# SuperKnob.net
KiCad netlist of a schematic drawn in Altium Designer
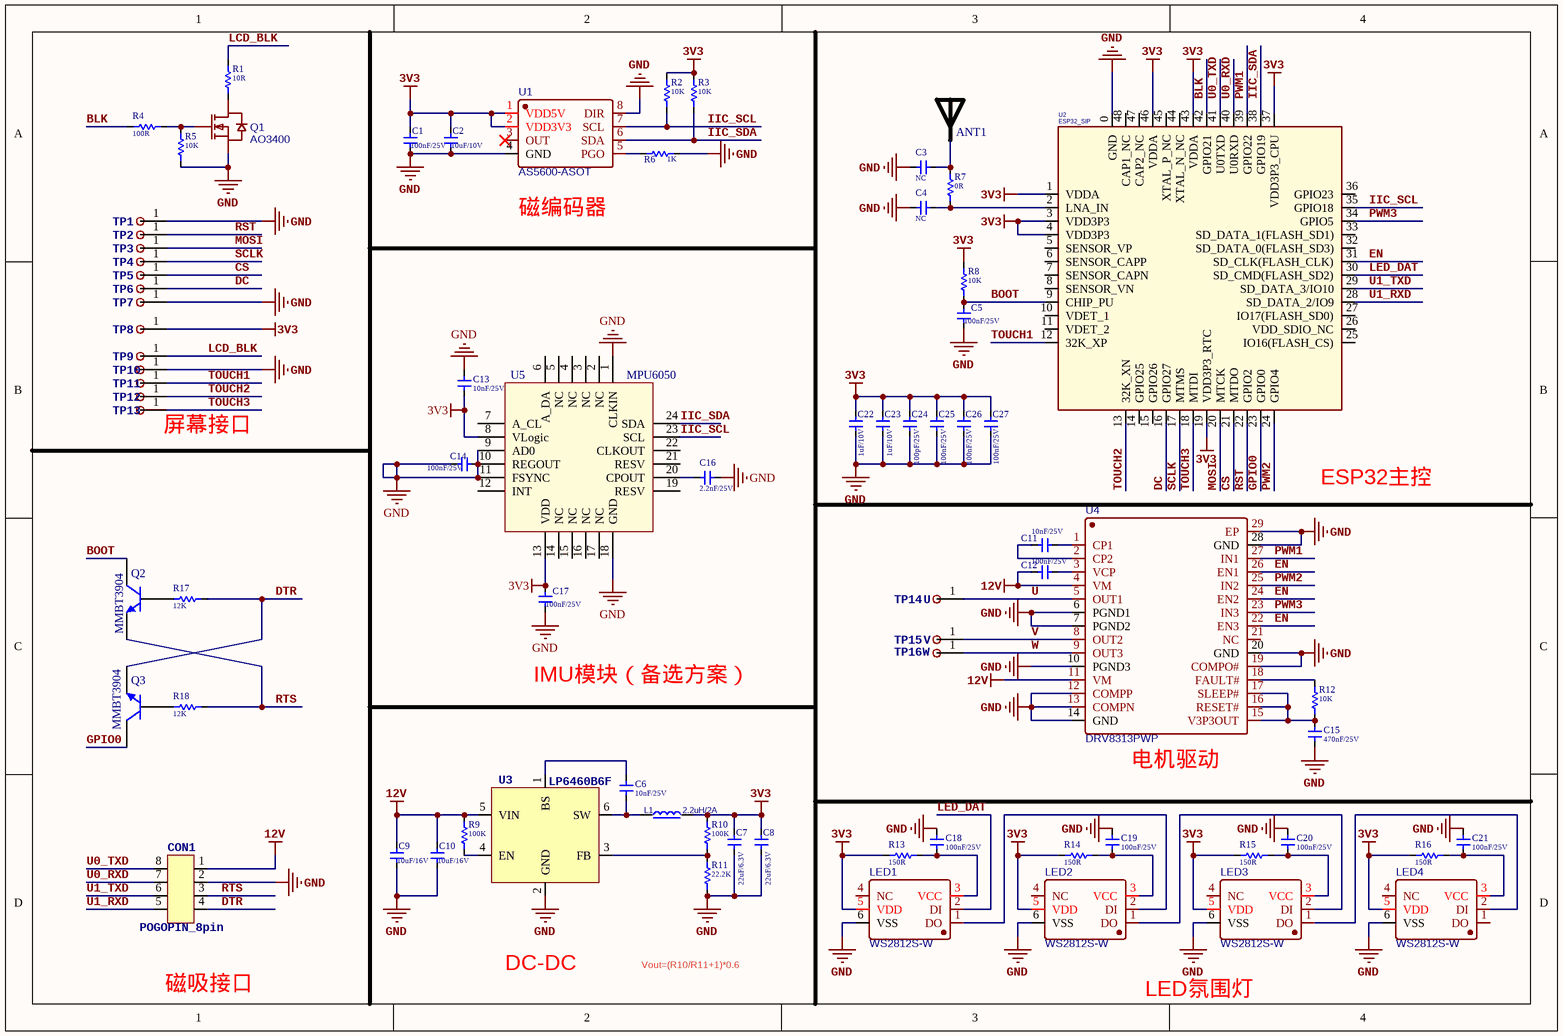
[diagram p0: SuperKnob.SchDoc]

(export (version "E")
  (design (tool "Eeschema 10.0.6"))
  (components
    (comp (ref "ANT1")
      (value "RAINSUN")
      (footprint "ANT-Rainsun-AN5120")
      (description "贴片天线")
      (libsource (lib "SuperKnob") (part "ANT-Rainsun-AP5120"))
    )
    (comp (ref "C1")
      (value "100nF/25V")
      (footprint "CAPC_0402")
      (description "贴片电容")
      (libsource (lib "SuperKnob") (part "电容-0402"))
    )
    (comp (ref "C2")
      (value "10uF/10V")
      (footprint "CAPC_0402")
      (description "贴片电容")
      (libsource (lib "SuperKnob") (part "电容-0402"))
    )
    (comp (ref "C3")
      (value "NC")
      (footprint "CAPC_0402")
      (description "贴片电容")
      (libsource (lib "SuperKnob") (part "电容-0402"))
    )
    (comp (ref "C4")
      (value "NC")
      (footprint "CAPC_0402")
      (description "贴片电容")
      (libsource (lib "SuperKnob") (part "电容-0402"))
    )
    (comp (ref "C5")
      (value "100nF/25V")
      (footprint "CAPC_0402")
      (description "贴片电容")
      (libsource (lib "SuperKnob") (part "电容-0402"))
    )
    (comp (ref "C6")
      (value "10nF/25V")
      (footprint "CAPC_0402")
      (description "贴片电容")
      (libsource (lib "SuperKnob") (part "电容-0402"))
    )
    (comp (ref "C7")
      (value "22uF/6.3V")
      (footprint "CAPC_0805")
      (description "贴片电容")
      (libsource (lib "SuperKnob") (part "电容-0402"))
    )
    (comp (ref "C8")
      (value "22uF/6.3V")
      (footprint "CAPC_0805")
      (description "贴片电容")
      (libsource (lib "SuperKnob") (part "电容-0402"))
    )
    (comp (ref "C9")
      (value "10uF/16V")
      (footprint "CAPC_0805")
      (description "贴片电容")
      (libsource (lib "SuperKnob") (part "电容-0402"))
    )
    (comp (ref "C10")
      (value "10uF/16V")
      (footprint "CAPC_0805")
      (description "贴片电容")
      (libsource (lib "SuperKnob") (part "电容-0402"))
    )
    (comp (ref "C11")
      (value "10nF/25V")
      (footprint "CAPC_0402")
      (description "贴片电容")
      (libsource (lib "SuperKnob") (part "电容-0402"))
    )
    (comp (ref "C12")
      (value "100nF/25V")
      (footprint "CAPC_0402")
      (description "贴片电容")
      (libsource (lib "SuperKnob") (part "电容-0402"))
    )
    (comp (ref "C13")
      (value "10nF/25V")
      (footprint "CAPC_0402")
      (description "贴片电容")
      (libsource (lib "SuperKnob") (part "电容-0402"))
    )
    (comp (ref "C14")
      (value "100nF/25V")
      (footprint "CAPC_0402")
      (description "贴片电容")
      (libsource (lib "SuperKnob") (part "电容-0402"))
    )
    (comp (ref "C15")
      (value "470nF/25V")
      (footprint "CAPC_0402")
      (description "贴片电容")
      (libsource (lib "SuperKnob") (part "电容-0402"))
    )
    (comp (ref "C16")
      (value "2.2nF/25V")
      (footprint "CAPC_0402")
      (description "贴片电容")
      (libsource (lib "SuperKnob") (part "电容-0402"))
    )
    (comp (ref "C17")
      (value "100nF/25V")
      (footprint "CAPC_0402")
      (description "贴片电容")
      (libsource (lib "SuperKnob") (part "电容-0402"))
    )
    (comp (ref "C18")
      (value "100nF/25V")
      (footprint "CAPC_0402")
      (description "贴片电容")
      (libsource (lib "SuperKnob") (part "电容-0402"))
    )
    (comp (ref "C19")
      (value "100nF/25V")
      (footprint "CAPC_0402")
      (description "贴片电容")
      (libsource (lib "SuperKnob") (part "电容-0402"))
    )
    (comp (ref "C20")
      (value "100nF/25V")
      (footprint "CAPC_0402")
      (description "贴片电容")
      (libsource (lib "SuperKnob") (part "电容-0402"))
    )
    (comp (ref "C21")
      (value "100nF/25V")
      (footprint "CAPC_0402")
      (description "贴片电容")
      (libsource (lib "SuperKnob") (part "电容-0402"))
    )
    (comp (ref "C22")
      (value "1uF/10V")
      (footprint "CAPC_0402")
      (description "贴片电容")
      (libsource (lib "SuperKnob") (part "电容-0402"))
    )
    (comp (ref "C23")
      (value "1uF/10V")
      (footprint "CAPC_0402")
      (description "贴片电容")
      (libsource (lib "SuperKnob") (part "电容-0402"))
    )
    (comp (ref "C24")
      (value "100pF/25V")
      (footprint "CAPC_0402")
      (description "贴片电容")
      (libsource (lib "SuperKnob") (part "电容-0402"))
    )
    (comp (ref "C25")
      (value "100nF/25V")
      (footprint "CAPC_0402")
      (description "贴片电容")
      (libsource (lib "SuperKnob") (part "电容-0402"))
    )
    (comp (ref "C26")
      (value "100nF/25V")
      (footprint "CAPC_0402")
      (description "贴片电容")
      (libsource (lib "SuperKnob") (part "电容-0402"))
    )
    (comp (ref "C27")
      (value "100nF/25V")
      (footprint "CAPC_0402")
      (description "贴片电容")
      (libsource (lib "SuperKnob") (part "电容-0402"))
    )
    (comp (ref "CON1")
      (value "POGOPIN_8pin")
      (footprint "POGOPIN_8pin")
      (description "磁吸连接器")
      (libsource (lib "SuperKnob") (part "POGOPIN_8pin"))
    )
    (comp (ref "L1")
      (value "2.2uH/2A")
      (footprint "Inductor_CD_43")
      (description "贴片电感")
      (libsource (lib "*") (part "PL4020"))
    )
    (comp (ref "LED1")
      (value "WS2812S-W")
      (footprint "LED-SMD_6P-L5.0-W5.0-TL")
      (fields (field (name "BOM_SUPPLIER PART") "C114584") (field (name "CONTRIBUTOR") "LCSC"))
      (libsource (lib "altium-import") (part "root_2_WS2812S-W_"))
    )
    (comp (ref "LED2")
      (value "WS2812S-W")
      (footprint "LED-SMD_6P-L5.0-W5.0-TL")
      (fields (field (name "BOM_SUPPLIER PART") "C114584") (field (name "CONTRIBUTOR") "LCSC"))
      (libsource (lib "altium-import") (part "root_2_WS2812S-W_"))
    )
    (comp (ref "LED3")
      (value "WS2812S-W")
      (footprint "LED-SMD_6P-L5.0-W5.0-TL")
      (fields (field (name "BOM_SUPPLIER PART") "C114584") (field (name "CONTRIBUTOR") "LCSC"))
      (libsource (lib "altium-import") (part "root_2_WS2812S-W_"))
    )
    (comp (ref "LED4")
      (value "WS2812S-W")
      (footprint "LED-SMD_6P-L5.0-W5.0-TL")
      (fields (field (name "BOM_SUPPLIER PART") "C114584") (field (name "CONTRIBUTOR") "LCSC"))
      (libsource (lib "altium-import") (part "root_2_WS2812S-W_"))
    )
    (comp (ref "Q1")
      (value "AO3400")
      (footprint "SOT23_3")
      (fields
        (field (name "BOM_SUPPLIER PART") "C2940037")
        (field (name "BOM_MANUFACTURER PART") "FH3400C")
        (field (name "CONTRIBUTOR") "LCSC")
      )
      (libsource (lib "altium-import") (part "root_0_FH3400C_"))
    )
    (comp (ref "Q2")
      (value "MMBT3904")
      (footprint "SOT23_3")
      (description "Surface mount NPN transistor, package SOT-23")
      (libsource (lib "MyPcbLib") (part "SMT_TRIODE_NPN"))
    )
    (comp (ref "Q3")
      (value "MMBT3904")
      (footprint "SOT23_3")
      (description "Surface mount NPN transistor, package SOT-23")
      (libsource (lib "MyPcbLib") (part "SMT_TRIODE_NPN"))
    )
    (comp (ref "R1")
      (value "10R")
      (footprint "RESC_0402")
      (description "贴片电阻")
      (libsource (lib "SuperKnob") (part "电阻-0402"))
    )
    (comp (ref "R2")
      (value "10K")
      (footprint "RESC_0402")
      (description "贴片电阻")
      (libsource (lib "SuperKnob") (part "电阻-0402"))
    )
    (comp (ref "R3")
      (value "10K")
      (footprint "RESC_0402")
      (description "贴片电阻")
      (libsource (lib "SuperKnob") (part "电阻-0402"))
    )
    (comp (ref "R4")
      (value "100R")
      (footprint "RESC_0402")
      (description "贴片电阻")
      (libsource (lib "SuperKnob") (part "电阻-0402"))
    )
    (comp (ref "R5")
      (value "10K")
      (footprint "RESC_0402")
      (description "贴片电阻")
      (libsource (lib "SuperKnob") (part "电阻-0402"))
    )
    (comp (ref "R6")
      (value "1K")
      (footprint "RESC_0402")
      (description "贴片电阻")
      (libsource (lib "SuperKnob") (part "电阻-0402"))
    )
    (comp (ref "R7")
      (value "0R")
      (footprint "RESC_0402")
      (description "贴片电阻")
      (libsource (lib "SuperKnob") (part "电阻-0402"))
    )
    (comp (ref "R8")
      (value "10K")
      (footprint "RESC_0402")
      (description "贴片电阻")
      (libsource (lib "SuperKnob") (part "电阻-0402"))
    )
    (comp (ref "R9")
      (value "100K")
      (footprint "RESC_0402")
      (description "贴片电阻")
      (libsource (lib "SuperKnob") (part "电阻-0402"))
    )
    (comp (ref "R10")
      (value "100K")
      (footprint "RESC_0402")
      (description "贴片电阻")
      (libsource (lib "SuperKnob") (part "电阻-0402"))
    )
    (comp (ref "R11")
      (value "22.2K")
      (footprint "RESC_0402")
      (description "贴片电阻")
      (libsource (lib "SuperKnob") (part "电阻-0402"))
    )
    (comp (ref "R12")
      (value "10K")
      (footprint "RESC_0402")
      (description "贴片电阻")
      (libsource (lib "SuperKnob") (part "电阻-0402"))
    )
    (comp (ref "R13")
      (value "150R")
      (footprint "RESC_0603")
      (description "贴片电阻")
      (libsource (lib "SuperKnob") (part "电阻-0402"))
    )
    (comp (ref "R14")
      (value "150R")
      (footprint "RESC_0603")
      (description "贴片电阻")
      (libsource (lib "SuperKnob") (part "电阻-0402"))
    )
    (comp (ref "R15")
      (value "150R")
      (footprint "RESC_0603")
      (description "贴片电阻")
      (libsource (lib "SuperKnob") (part "电阻-0402"))
    )
    (comp (ref "R16")
      (value "150R")
      (footprint "RESC_0603")
      (description "贴片电阻")
      (libsource (lib "SuperKnob") (part "电阻-0402"))
    )
    (comp (ref "R17")
      (value "12K")
      (footprint "RESC_0402")
      (description "贴片电阻")
      (libsource (lib "SuperKnob") (part "电阻-0402"))
    )
    (comp (ref "R18")
      (value "12K")
      (footprint "RESC_0402")
      (description "贴片电阻")
      (libsource (lib "SuperKnob") (part "电阻-0402"))
    )
    (comp (ref "TP1")
      (value "TP")
      (footprint "TP")
      (description "测试点")
      (libsource (lib "SuperKnob") (part "TP"))
    )
    (comp (ref "TP2")
      (value "TP")
      (footprint "TP")
      (description "测试点")
      (libsource (lib "SuperKnob") (part "TP"))
    )
    (comp (ref "TP3")
      (value "TP")
      (footprint "TP")
      (description "测试点")
      (libsource (lib "SuperKnob") (part "TP"))
    )
    (comp (ref "TP4")
      (value "TP")
      (footprint "TP")
      (description "测试点")
      (libsource (lib "SuperKnob") (part "TP"))
    )
    (comp (ref "TP5")
      (value "TP")
      (footprint "TP")
      (description "测试点")
      (libsource (lib "SuperKnob") (part "TP"))
    )
    (comp (ref "TP6")
      (value "TP")
      (footprint "TP")
      (description "测试点")
      (libsource (lib "SuperKnob") (part "TP"))
    )
    (comp (ref "TP7")
      (value "TP")
      (footprint "TP")
      (description "测试点")
      (libsource (lib "SuperKnob") (part "TP"))
    )
    (comp (ref "TP8")
      (value "TP")
      (footprint "TP")
      (description "测试点")
      (libsource (lib "SuperKnob") (part "TP"))
    )
    (comp (ref "TP9")
      (value "TP")
      (footprint "TP")
      (description "测试点")
      (libsource (lib "SuperKnob") (part "TP"))
    )
    (comp (ref "TP10")
      (value "TP")
      (footprint "TP")
      (description "测试点")
      (libsource (lib "SuperKnob") (part "TP"))
    )
    (comp (ref "TP11")
      (value "TP")
      (footprint "TP")
      (description "测试点")
      (libsource (lib "SuperKnob") (part "TP"))
    )
    (comp (ref "TP12")
      (value "TP")
      (footprint "TP")
      (description "测试点")
      (libsource (lib "SuperKnob") (part "TP"))
    )
    (comp (ref "TP13")
      (value "TP")
      (footprint "TP")
      (description "测试点")
      (libsource (lib "SuperKnob") (part "TP"))
    )
    (comp (ref "TP14")
      (value "U")
      (footprint "TP")
      (description "测试点")
      (libsource (lib "SuperKnob") (part "TP"))
    )
    (comp (ref "TP15")
      (value "V")
      (footprint "TP")
      (description "测试点")
      (libsource (lib "SuperKnob") (part "TP"))
    )
    (comp (ref "TP16")
      (value "W")
      (footprint "TP")
      (description "测试点")
      (libsource (lib "SuperKnob") (part "TP"))
    )
    (comp (ref "U1")
      (value "AS5600-ASOT")
      (footprint "SOIC_8")
      (description "磁编码器")
      (fields (field (name "BOM_SUPPLIER PART") "C499458") (field (name "CONTRIBUTOR") "LCSC"))
      (libsource (lib "SuperKnob") (part "AS5600-ASOT"))
    )
    (comp (ref "U2")
      (value "ESP32_SIP")
      (footprint "QFN-48_7X7")
      (description "主控芯片")
      (libsource (lib "SuperKnob") (part "ESP32-PICO"))
    )
    (comp (ref "U3")
      (value "LP6460B6F")
      (footprint "SOT23_6")
      (description "DC-DC芯片")
      (libsource (lib "SuperKnob") (part "LP6460B6F"))
    )
    (comp (ref "U4")
      (value "DRV8313PWP")
      (footprint "TSSOP_28")
      (description "驱动芯片")
      (fields (field (name "BOM_SUPPLIER PART") "C2863441") (field (name "CONTRIBUTOR") "LCSC"))
      (libsource (lib "SuperKnob") (part "DRV8313PWP"))
    )
    (comp (ref "U5")
      (value "MPU6050")
      (footprint "QFN-24")
      (description "六轴传感器")
      (libsource (lib "mLib") (part "MPU6050"))
    )
  )
  (nets
    (net (code "1") (name "/BLK") (class "Default")
      (node (ref "R4") (pin "1") (pinfunction "1_1") (pintype "passive"))
      (node (ref "U2") (pin "42") (pinfunction "GPIO21_42") (pintype "passive"))
    )
    (net (code "2") (name "/BOOT") (class "Default")
      (node (ref "C5") (pin "2") (pinfunction "2_2") (pintype "passive"))
      (node (ref "Q2") (pin "3") (pinfunction "C_3") (pintype "passive"))
      (node (ref "R8") (pin "2") (pinfunction "2_2") (pintype "passive"))
      (node (ref "U2") (pin "9") (pinfunction "CHIP_PU_9") (pintype "passive"))
    )
    (net (code "3") (name "/CS") (class "Default")
      (node (ref "TP5") (pin "1") (pinfunction "1_1") (pintype "passive"))
      (node (ref "U2") (pin "21") (pinfunction "MTDO_21") (pintype "passive"))
    )
    (net (code "4") (name "/DC") (class "Default")
      (node (ref "TP6") (pin "1") (pinfunction "1_1") (pintype "passive"))
      (node (ref "U2") (pin "16") (pinfunction "GPIO27_16") (pintype "passive"))
    )
    (net (code "5") (name "/DTR") (class "Default")
      (node (ref "CON1") (pin "4") (pinfunction "4_4") (pintype "passive"))
      (node (ref "Q3") (pin "2") (pinfunction "E_2") (pintype "passive"))
      (node (ref "R17") (pin "2") (pinfunction "2_2") (pintype "passive"))
    )
    (net (code "6") (name "/EN") (class "Default")
      (node (ref "U2") (pin "31") (pinfunction "SD_CLK(FLASH_CLK)_31") (pintype "passive"))
      (node (ref "U4") (pin "22") (pinfunction "EN3_22") (pintype "passive"))
      (node (ref "U4") (pin "24") (pinfunction "EN2_24") (pintype "passive"))
      (node (ref "U4") (pin "26") (pinfunction "EN1_26") (pintype "passive"))
    )
    (net (code "7") (name "/GPIO0") (class "Default")
      (node (ref "Q3") (pin "3") (pinfunction "C_3") (pintype "passive"))
      (node (ref "U2") (pin "23") (pinfunction "GPIO0_23") (pintype "passive"))
    )
    (net (code "8") (name "/IIC_SCL") (class "Default")
      (node (ref "R2") (pin "1") (pinfunction "1_1") (pintype "passive"))
      (node (ref "U1") (pin "7") (pinfunction "SCL_7") (pintype "passive"))
      (node (ref "U2") (pin "35") (pinfunction "GPIO18_35") (pintype "passive"))
      (node (ref "U5") (pin "23") (pinfunction "SCL_23") (pintype "passive"))
    )
    (net (code "9") (name "/IIC_SDA") (class "Default")
      (node (ref "R3") (pin "1") (pinfunction "1_1") (pintype "passive"))
      (node (ref "U1") (pin "6") (pinfunction "SDA_6") (pintype "passive"))
      (node (ref "U2") (pin "38") (pinfunction "GPIO19_38") (pintype "passive"))
      (node (ref "U5") (pin "24") (pinfunction "SDA_24") (pintype "passive"))
    )
    (net (code "10") (name "/LCD_BLK") (class "Default")
      (node (ref "R1") (pin "2") (pinfunction "2_2") (pintype "passive"))
      (node (ref "TP9") (pin "1") (pinfunction "1_1") (pintype "passive"))
    )
    (net (code "11") (name "/LED_DAT") (class "Default")
      (node (ref "LED1") (pin "2") (pinfunction "DI_2") (pintype "passive"))
      (node (ref "U2") (pin "30") (pinfunction "SD_CMD(FLASH_SD2)_30") (pintype "passive"))
    )
    (net (code "12") (name "/MOSI") (class "Default")
      (node (ref "TP3") (pin "1") (pinfunction "1_1") (pintype "passive"))
      (node (ref "U2") (pin "20") (pinfunction "MTCK_20") (pintype "passive"))
    )
    (net (code "13") (name "/PWM1") (class "Default")
      (node (ref "U2") (pin "39") (pinfunction "GPIO22_39") (pintype "passive"))
      (node (ref "U4") (pin "27") (pinfunction "IN1_27") (pintype "passive"))
    )
    (net (code "14") (name "/PWM2") (class "Default")
      (node (ref "U2") (pin "24") (pinfunction "GPIO4_24") (pintype "passive"))
      (node (ref "U4") (pin "25") (pinfunction "IN2_25") (pintype "passive"))
    )
    (net (code "15") (name "/PWM3") (class "Default")
      (node (ref "U2") (pin "34") (pinfunction "GPIO5_34") (pintype "passive"))
      (node (ref "U4") (pin "23") (pinfunction "IN3_23") (pintype "passive"))
    )
    (net (code "16") (name "/RST") (class "Default")
      (node (ref "TP2") (pin "1") (pinfunction "1_1") (pintype "passive"))
      (node (ref "U2") (pin "22") (pinfunction "GPIO2_22") (pintype "passive"))
    )
    (net (code "17") (name "/RTS") (class "Default")
      (node (ref "CON1") (pin "3") (pinfunction "3_3") (pintype "passive"))
      (node (ref "Q2") (pin "2") (pinfunction "E_2") (pintype "passive"))
      (node (ref "R18") (pin "2") (pinfunction "2_2") (pintype "passive"))
    )
    (net (code "18") (name "/SCLK") (class "Default")
      (node (ref "TP4") (pin "1") (pinfunction "1_1") (pintype "passive"))
      (node (ref "U2") (pin "17") (pinfunction "MTMS_17") (pintype "passive"))
    )
    (net (code "19") (name "/TOUCH1") (class "Default")
      (node (ref "TP11") (pin "1") (pinfunction "1_1") (pintype "passive"))
      (node (ref "U2") (pin "12") (pinfunction "32K_XP_12") (pintype "passive"))
    )
    (net (code "20") (name "/TOUCH2") (class "Default")
      (node (ref "TP12") (pin "1") (pinfunction "1_1") (pintype "passive"))
      (node (ref "U2") (pin "13") (pinfunction "32K_XN_13") (pintype "passive"))
    )
    (net (code "21") (name "/TOUCH3") (class "Default")
      (node (ref "TP13") (pin "1") (pinfunction "1_1") (pintype "passive"))
      (node (ref "U2") (pin "18") (pinfunction "MTDI_18") (pintype "passive"))
    )
    (net (code "22") (name "/U") (class "Default")
      (node (ref "TP14") (pin "1") (pinfunction "1_1") (pintype "passive"))
      (node (ref "U4") (pin "5") (pinfunction "OUT1_5") (pintype "passive"))
    )
    (net (code "23") (name "/U0_RXD") (class "Default")
      (node (ref "CON1") (pin "7") (pinfunction "7_7") (pintype "passive"))
      (node (ref "U2") (pin "40") (pinfunction "U0RXD_40") (pintype "power_in"))
    )
    (net (code "24") (name "/U0_TXD") (class "Default")
      (node (ref "CON1") (pin "8") (pinfunction "8_8") (pintype "passive"))
      (node (ref "U2") (pin "41") (pinfunction "U0TXD_41") (pintype "power_in"))
    )
    (net (code "25") (name "/U1_RXD") (class "Default")
      (node (ref "CON1") (pin "5") (pinfunction "5_5") (pintype "passive"))
      (node (ref "U2") (pin "28") (pinfunction "SD_DATA_2/IO9_28") (pintype "passive"))
    )
    (net (code "26") (name "/U1_TXD") (class "Default")
      (node (ref "CON1") (pin "6") (pinfunction "6_6") (pintype "passive"))
      (node (ref "U2") (pin "29") (pinfunction "SD_DATA_3/IO10_29") (pintype "passive"))
    )
    (net (code "27") (name "/V") (class "Default")
      (node (ref "TP15") (pin "1") (pinfunction "1_1") (pintype "passive"))
      (node (ref "U4") (pin "8") (pinfunction "OUT2_8") (pintype "passive"))
    )
    (net (code "28") (name "/W") (class "Default")
      (node (ref "TP16") (pin "1") (pinfunction "1_1") (pintype "passive"))
      (node (ref "U4") (pin "9") (pinfunction "OUT3_9") (pintype "passive"))
    )
    (net (code "29") (name "3V3") (class "Default")
      (node (ref "C1") (pin "2") (pinfunction "2_2") (pintype "passive"))
      (node (ref "C13") (pin "2") (pinfunction "2_2") (pintype "passive"))
      (node (ref "C17") (pin "2") (pinfunction "2_2") (pintype "passive"))
      (node (ref "C2") (pin "2") (pinfunction "2_2") (pintype "passive"))
      (node (ref "C22") (pin "2") (pinfunction "2_2") (pintype "passive"))
      (node (ref "C23") (pin "2") (pinfunction "2_2") (pintype "passive"))
      (node (ref "C24") (pin "1") (pinfunction "1_1") (pintype "passive"))
      (node (ref "C25") (pin "2") (pinfunction "2_2") (pintype "passive"))
      (node (ref "C26") (pin "2") (pinfunction "2_2") (pintype "passive"))
      (node (ref "C27") (pin "2") (pinfunction "2_2") (pintype "passive"))
      (node (ref "C7") (pin "2") (pinfunction "2_2") (pintype "passive"))
      (node (ref "C8") (pin "2") (pinfunction "2_2") (pintype "passive"))
      (node (ref "L1") (pin "1") (pinfunction "1_1") (pintype "passive"))
      (node (ref "LED1") (pin "5") (pinfunction "VDD_5") (pintype "passive"))
      (node (ref "LED2") (pin "5") (pinfunction "VDD_5") (pintype "passive"))
      (node (ref "LED3") (pin "5") (pinfunction "VDD_5") (pintype "passive"))
      (node (ref "LED4") (pin "5") (pinfunction "VDD_5") (pintype "passive"))
      (node (ref "R10") (pin "1") (pinfunction "1_1") (pintype "passive"))
      (node (ref "R13") (pin "1") (pinfunction "1_1") (pintype "passive"))
      (node (ref "R14") (pin "1") (pinfunction "1_1") (pintype "passive"))
      (node (ref "R15") (pin "1") (pinfunction "1_1") (pintype "passive"))
      (node (ref "R16") (pin "1") (pinfunction "1_1") (pintype "passive"))
      (node (ref "R2") (pin "2") (pinfunction "2_2") (pintype "passive"))
      (node (ref "R3") (pin "2") (pinfunction "2_2") (pintype "passive"))
      (node (ref "R8") (pin "1") (pinfunction "1_1") (pintype "passive"))
      (node (ref "TP8") (pin "1") (pinfunction "1_1") (pintype "passive"))
      (node (ref "U1") (pin "1") (pinfunction "VDD5V_1") (pintype "passive"))
      (node (ref "U1") (pin "2") (pinfunction "VDD3V3_2") (pintype "passive"))
      (node (ref "U2") (pin "1") (pinfunction "VDDA_1") (pintype "power_in"))
      (node (ref "U2") (pin "19") (pinfunction "VDD3P3_RTC_19") (pintype "power_in"))
      (node (ref "U2") (pin "3") (pinfunction "VDD3P3_3") (pintype "power_in"))
      (node (ref "U2") (pin "37") (pinfunction "VDD3P3_CPU_37") (pintype "power_in"))
      (node (ref "U2") (pin "4") (pinfunction "VDD3P3_4") (pintype "power_in"))
      (node (ref "U2") (pin "43") (pinfunction "VDDA_43") (pintype "power_in"))
      (node (ref "U2") (pin "46") (pinfunction "VDDA_46") (pintype "power_in"))
      (node (ref "U5") (pin "13") (pinfunction "VDD_13") (pintype "passive"))
      (node (ref "U5") (pin "8") (pinfunction "VLogic_8") (pintype "passive"))
    )
    (net (code "30") (name "12V") (class "Default")
      (node (ref "C10") (pin "2") (pinfunction "2_2") (pintype "passive"))
      (node (ref "C12") (pin "1") (pinfunction "1_1") (pintype "passive"))
      (node (ref "C9") (pin "2") (pinfunction "2_2") (pintype "passive"))
      (node (ref "CON1") (pin "1") (pinfunction "1_1") (pintype "passive"))
      (node (ref "R9") (pin "1") (pinfunction "1_1") (pintype "passive"))
      (node (ref "U3") (pin "5") (pinfunction "VIN_5") (pintype "passive"))
      (node (ref "U4") (pin "11") (pinfunction "VM_11") (pintype "passive"))
      (node (ref "U4") (pin "4") (pinfunction "VM_4") (pintype "passive"))
    )
    (net (code "31") (name "GND") (class "Default")
      (node (ref "C1") (pin "1") (pinfunction "1_1") (pintype "passive"))
      (node (ref "C10") (pin "1") (pinfunction "1_1") (pintype "passive"))
      (node (ref "C13") (pin "1") (pinfunction "1_1") (pintype "passive"))
      (node (ref "C14") (pin "1") (pinfunction "1_1") (pintype "passive"))
      (node (ref "C14") (pin "2") (pinfunction "2_2") (pintype "passive"))
      (node (ref "C15") (pin "1") (pinfunction "1_1") (pintype "passive"))
      (node (ref "C16") (pin "2") (pinfunction "2_2") (pintype "passive"))
      (node (ref "C17") (pin "1") (pinfunction "1_1") (pintype "passive"))
      (node (ref "C18") (pin "2") (pinfunction "2_2") (pintype "passive"))
      (node (ref "C19") (pin "2") (pinfunction "2_2") (pintype "passive"))
      (node (ref "C2") (pin "1") (pinfunction "1_1") (pintype "passive"))
      (node (ref "C20") (pin "1") (pinfunction "1_1") (pintype "passive"))
      (node (ref "C21") (pin "1") (pinfunction "1_1") (pintype "passive"))
      (node (ref "C22") (pin "1") (pinfunction "1_1") (pintype "passive"))
      (node (ref "C23") (pin "1") (pinfunction "1_1") (pintype "passive"))
      (node (ref "C24") (pin "2") (pinfunction "2_2") (pintype "passive"))
      (node (ref "C25") (pin "1") (pinfunction "1_1") (pintype "passive"))
      (node (ref "C26") (pin "1") (pinfunction "1_1") (pintype "passive"))
      (node (ref "C27") (pin "1") (pinfunction "1_1") (pintype "passive"))
      (node (ref "C3") (pin "1") (pinfunction "1_1") (pintype "passive"))
      (node (ref "C4") (pin "1") (pinfunction "1_1") (pintype "passive"))
      (node (ref "C5") (pin "1") (pinfunction "1_1") (pintype "passive"))
      (node (ref "C7") (pin "1") (pinfunction "1_1") (pintype "passive"))
      (node (ref "C8") (pin "1") (pinfunction "1_1") (pintype "passive"))
      (node (ref "C9") (pin "1") (pinfunction "1_1") (pintype "passive"))
      (node (ref "CON1") (pin "2") (pinfunction "2_2") (pintype "passive"))
      (node (ref "LED1") (pin "6") (pinfunction "VSS_6") (pintype "passive"))
      (node (ref "LED2") (pin "6") (pinfunction "VSS_6") (pintype "passive"))
      (node (ref "LED3") (pin "6") (pinfunction "VSS_6") (pintype "passive"))
      (node (ref "LED4") (pin "6") (pinfunction "VSS_6") (pintype "passive"))
      (node (ref "Q1") (pin "2") (pinfunction "S_2") (pintype "passive"))
      (node (ref "R11") (pin "2") (pinfunction "2_2") (pintype "passive"))
      (node (ref "R5") (pin "2") (pinfunction "2_2") (pintype "passive"))
      (node (ref "R6") (pin "2") (pinfunction "2_2") (pintype "passive"))
      (node (ref "TP1") (pin "1") (pinfunction "1_1") (pintype "passive"))
      (node (ref "TP10") (pin "1") (pinfunction "1_1") (pintype "passive"))
      (node (ref "TP7") (pin "1") (pinfunction "1_1") (pintype "passive"))
      (node (ref "U1") (pin "4") (pinfunction "GND_4") (pintype "passive"))
      (node (ref "U1") (pin "8") (pinfunction "DIR_8") (pintype "passive"))
      (node (ref "U2") (pin "0") (pinfunction "GND_0") (pintype "power_in"))
      (node (ref "U3") (pin "2") (pinfunction "GND_2") (pintype "passive"))
      (node (ref "U4") (pin "10") (pinfunction "PGND3_10") (pintype "passive"))
      (node (ref "U4") (pin "12") (pinfunction "COMPP_12") (pintype "passive"))
      (node (ref "U4") (pin "13") (pinfunction "COMPN_13") (pintype "passive"))
      (node (ref "U4") (pin "14") (pinfunction "GND_14") (pintype "passive"))
      (node (ref "U4") (pin "19") (pinfunction "COMPO#_19") (pintype "passive"))
      (node (ref "U4") (pin "20") (pinfunction "GND_20") (pintype "passive"))
      (node (ref "U4") (pin "28") (pinfunction "GND_28") (pintype "passive"))
      (node (ref "U4") (pin "29") (pinfunction "EP_29") (pintype "passive"))
      (node (ref "U4") (pin "6") (pinfunction "PGND1_6") (pintype "passive"))
      (node (ref "U4") (pin "7") (pinfunction "PGND2_7") (pintype "passive"))
      (node (ref "U5") (pin "1") (pinfunction "CLKIN_1") (pintype "passive"))
      (node (ref "U5") (pin "10") (pinfunction "REGOUT_10") (pintype "passive"))
      (node (ref "U5") (pin "11") (pinfunction "FSYNC_11") (pintype "passive"))
      (node (ref "U5") (pin "18") (pinfunction "GND_18") (pintype "passive"))
      (node (ref "U5") (pin "9") (pinfunction "AD0_9") (pintype "passive"))
    )
    (net (code "32") (name "Net-(ANT1-Pad1)") (class "Default")
      (node (ref "ANT1") (pin "1") (pinfunction "1_1") (pintype "passive"))
      (node (ref "C3") (pin "2") (pinfunction "2_2") (pintype "passive"))
      (node (ref "R7") (pin "1") (pinfunction "1_1") (pintype "passive"))
    )
    (net (code "33") (name "Net-(LED1-DO)") (class "Default")
      (node (ref "LED1") (pin "1") (pinfunction "DO_1") (pintype "passive"))
      (node (ref "LED2") (pin "2") (pinfunction "DI_2") (pintype "passive"))
    )
    (net (code "34") (name "Net-(LED1-VCC)") (class "Default")
      (node (ref "C18") (pin "1") (pinfunction "1_1") (pintype "passive"))
      (node (ref "LED1") (pin "3") (pinfunction "VCC_3") (pintype "passive"))
      (node (ref "R13") (pin "2") (pinfunction "2_2") (pintype "passive"))
    )
    (net (code "35") (name "Net-(LED2-DO)") (class "Default")
      (node (ref "LED2") (pin "1") (pinfunction "DO_1") (pintype "passive"))
      (node (ref "LED3") (pin "2") (pinfunction "DI_2") (pintype "passive"))
    )
    (net (code "36") (name "Net-(LED2-VCC)") (class "Default")
      (node (ref "C19") (pin "1") (pinfunction "1_1") (pintype "passive"))
      (node (ref "LED2") (pin "3") (pinfunction "VCC_3") (pintype "passive"))
      (node (ref "R14") (pin "2") (pinfunction "2_2") (pintype "passive"))
    )
    (net (code "37") (name "Net-(LED3-DO)") (class "Default")
      (node (ref "LED3") (pin "1") (pinfunction "DO_1") (pintype "passive"))
      (node (ref "LED4") (pin "2") (pinfunction "DI_2") (pintype "passive"))
    )
    (net (code "38") (name "Net-(LED3-VCC)") (class "Default")
      (node (ref "C20") (pin "2") (pinfunction "2_2") (pintype "passive"))
      (node (ref "LED3") (pin "3") (pinfunction "VCC_3") (pintype "passive"))
      (node (ref "R15") (pin "2") (pinfunction "2_2") (pintype "passive"))
    )
    (net (code "39") (name "Net-(LED4-VCC)") (class "Default")
      (node (ref "C21") (pin "2") (pinfunction "2_2") (pintype "passive"))
      (node (ref "LED4") (pin "3") (pinfunction "VCC_3") (pintype "passive"))
      (node (ref "R16") (pin "2") (pinfunction "2_2") (pintype "passive"))
    )
    (net (code "40") (name "Net-(Q1-D)") (class "Default")
      (node (ref "Q1") (pin "3") (pinfunction "D_3") (pintype "passive"))
      (node (ref "R1") (pin "1") (pinfunction "1_1") (pintype "passive"))
    )
    (net (code "41") (name "Net-(Q1-G)") (class "Default")
      (node (ref "Q1") (pin "1") (pinfunction "G_1") (pintype "passive"))
      (node (ref "R4") (pin "2") (pinfunction "2_2") (pintype "passive"))
      (node (ref "R5") (pin "1") (pinfunction "1_1") (pintype "passive"))
    )
    (net (code "42") (name "Net-(Q2-B)") (class "Default")
      (node (ref "Q2") (pin "1") (pinfunction "B_1") (pintype "passive"))
      (node (ref "R17") (pin "1") (pinfunction "1_1") (pintype "passive"))
    )
    (net (code "43") (name "Net-(Q3-B)") (class "Default")
      (node (ref "Q3") (pin "1") (pinfunction "B_1") (pintype "passive"))
      (node (ref "R18") (pin "1") (pinfunction "1_1") (pintype "passive"))
    )
    (net (code "44") (name "Net-(U1-PGO)") (class "Default")
      (node (ref "R6") (pin "1") (pinfunction "1_1") (pintype "passive"))
      (node (ref "U1") (pin "5") (pinfunction "PGO_5") (pintype "passive"))
    )
    (net (code "45") (name "Net-(U2-LNA_IN)") (class "Default")
      (node (ref "C4") (pin "2") (pinfunction "2_2") (pintype "passive"))
      (node (ref "R7") (pin "2") (pinfunction "2_2") (pintype "passive"))
      (node (ref "U2") (pin "2") (pinfunction "LNA_IN_2") (pintype "passive"))
    )
    (net (code "46") (name "Net-(U3-BS)") (class "Default")
      (node (ref "C6") (pin "2") (pinfunction "2_2") (pintype "passive"))
      (node (ref "U3") (pin "1") (pinfunction "BS_1") (pintype "passive"))
    )
    (net (code "47") (name "Net-(U3-EN)") (class "Default")
      (node (ref "R9") (pin "2") (pinfunction "2_2") (pintype "passive"))
      (node (ref "U3") (pin "4") (pinfunction "EN_4") (pintype "passive"))
    )
    (net (code "48") (name "Net-(U3-FB)") (class "Default")
      (node (ref "R10") (pin "2") (pinfunction "2_2") (pintype "passive"))
      (node (ref "R11") (pin "1") (pinfunction "1_1") (pintype "passive"))
      (node (ref "U3") (pin "3") (pinfunction "FB_3") (pintype "passive"))
    )
    (net (code "49") (name "Net-(U3-SW)") (class "Default")
      (node (ref "C6") (pin "1") (pinfunction "1_1") (pintype "passive"))
      (node (ref "L1") (pin "2") (pinfunction "2_2") (pintype "passive"))
      (node (ref "U3") (pin "6") (pinfunction "SW_6") (pintype "passive"))
    )
    (net (code "50") (name "Net-(U4-CP1)") (class "Default")
      (node (ref "C11") (pin "2") (pinfunction "2_2") (pintype "passive"))
      (node (ref "U4") (pin "1") (pinfunction "CP1_1") (pintype "passive"))
    )
    (net (code "51") (name "Net-(U4-CP2)") (class "Default")
      (node (ref "C11") (pin "1") (pinfunction "1_1") (pintype "passive"))
      (node (ref "U4") (pin "2") (pinfunction "CP2_2") (pintype "passive"))
    )
    (net (code "52") (name "Net-(U4-FAULT#)") (class "Default")
      (node (ref "R12") (pin "1") (pinfunction "1_1") (pintype "passive"))
      (node (ref "U4") (pin "18") (pinfunction "FAULT#_18") (pintype "passive"))
    )
    (net (code "53") (name "Net-(U4-RESET#)") (class "Default")
      (node (ref "C15") (pin "2") (pinfunction "2_2") (pintype "passive"))
      (node (ref "R12") (pin "2") (pinfunction "2_2") (pintype "passive"))
      (node (ref "U4") (pin "15") (pinfunction "V3P3OUT_15") (pintype "passive"))
      (node (ref "U4") (pin "16") (pinfunction "RESET#_16") (pintype "passive"))
      (node (ref "U4") (pin "17") (pinfunction "SLEEP#_17") (pintype "passive"))
    )
    (net (code "54") (name "Net-(U4-VCP)") (class "Default")
      (node (ref "C12") (pin "2") (pinfunction "2_2") (pintype "passive"))
      (node (ref "U4") (pin "3") (pinfunction "VCP_3") (pintype "passive"))
    )
    (net (code "55") (name "Net-(U5-CPOUT)") (class "Default")
      (node (ref "C16") (pin "1") (pinfunction "1_1") (pintype "passive"))
      (node (ref "U5") (pin "20") (pinfunction "CPOUT_20") (pintype "passive"))
    )
    (net (code "56") (name "unconnected-(LED1-NC-Pad4)") (class "Default")
      (node (ref "LED1") (pin "4") (pinfunction "NC_4") (pintype "passive"))
    )
    (net (code "57") (name "unconnected-(LED2-NC-Pad4)") (class "Default")
      (node (ref "LED2") (pin "4") (pinfunction "NC_4") (pintype "passive"))
    )
    (net (code "58") (name "unconnected-(LED3-NC-Pad4)") (class "Default")
      (node (ref "LED3") (pin "4") (pinfunction "NC_4") (pintype "passive"))
    )
    (net (code "59") (name "unconnected-(LED4-DO-Pad1)") (class "Default")
      (node (ref "LED4") (pin "1") (pinfunction "DO_1") (pintype "passive"))
    )
    (net (code "60") (name "unconnected-(LED4-NC-Pad4)") (class "Default")
      (node (ref "LED4") (pin "4") (pinfunction "NC_4") (pintype "passive"))
    )
    (net (code "61") (name "unconnected-(U1-OUT-Pad3)") (class "Default")
      (node (ref "U1") (pin "3") (pinfunction "OUT_3") (pintype "passive+no_connect"))
    )
    (net (code "62") (name "unconnected-(U2-CAP1_NC-Pad48)") (class "Default")
      (node (ref "U2") (pin "48") (pinfunction "CAP1_NC_48") (pintype "passive"))
    )
    (net (code "63") (name "unconnected-(U2-CAP2_NC-Pad47)") (class "Default")
      (node (ref "U2") (pin "47") (pinfunction "CAP2_NC_47") (pintype "passive"))
    )
    (net (code "64") (name "unconnected-(U2-GPIO23-Pad36)") (class "Default")
      (node (ref "U2") (pin "36") (pinfunction "GPIO23_36") (pintype "passive"))
    )
    (net (code "65") (name "unconnected-(U2-GPIO25-Pad14)") (class "Default")
      (node (ref "U2") (pin "14") (pinfunction "GPIO25_14") (pintype "passive"))
    )
    (net (code "66") (name "unconnected-(U2-GPIO26-Pad15)") (class "Default")
      (node (ref "U2") (pin "15") (pinfunction "GPIO26_15") (pintype "passive"))
    )
    (net (code "67") (name "unconnected-(U2-IO16(FLASH_CS)-Pad25)") (class "Default")
      (node (ref "U2") (pin "25") (pinfunction "IO16(FLASH_CS)_25") (pintype "passive"))
    )
    (net (code "68") (name "unconnected-(U2-IO17(FLASH_SD0)-Pad27)") (class "Default")
      (node (ref "U2") (pin "27") (pinfunction "IO17(FLASH_SD0)_27") (pintype "passive"))
    )
    (net (code "69") (name "unconnected-(U2-SD_DATA_0(FLASH_SD3)-Pad32)") (class "Default")
      (node (ref "U2") (pin "32") (pinfunction "SD_DATA_0(FLASH_SD3)_32") (pintype "passive"))
    )
    (net (code "70") (name "unconnected-(U2-SD_DATA_1(FLASH_SD1)-Pad33)") (class "Default")
      (node (ref "U2") (pin "33") (pinfunction "SD_DATA_1(FLASH_SD1)_33") (pintype "passive"))
    )
    (net (code "71") (name "unconnected-(U2-SENSOR_CAPN-Pad7)") (class "Default")
      (node (ref "U2") (pin "7") (pinfunction "SENSOR_CAPN_7") (pintype "passive"))
    )
    (net (code "72") (name "unconnected-(U2-SENSOR_CAPP-Pad6)") (class "Default")
      (node (ref "U2") (pin "6") (pinfunction "SENSOR_CAPP_6") (pintype "passive"))
    )
    (net (code "73") (name "unconnected-(U2-SENSOR_VN-Pad8)") (class "Default")
      (node (ref "U2") (pin "8") (pinfunction "SENSOR_VN_8") (pintype "passive"))
    )
    (net (code "74") (name "unconnected-(U2-SENSOR_VP-Pad5)") (class "Default")
      (node (ref "U2") (pin "5") (pinfunction "SENSOR_VP_5") (pintype "passive"))
    )
    (net (code "75") (name "unconnected-(U2-VDD_SDIO_NC-Pad26)") (class "Default")
      (node (ref "U2") (pin "26") (pinfunction "VDD_SDIO_NC_26") (pintype "passive"))
    )
    (net (code "76") (name "unconnected-(U2-VDET_1-Pad10)") (class "Default")
      (node (ref "U2") (pin "10") (pinfunction "VDET_1_10") (pintype "passive"))
    )
    (net (code "77") (name "unconnected-(U2-VDET_2-Pad11)") (class "Default")
      (node (ref "U2") (pin "11") (pinfunction "VDET_2_11") (pintype "passive"))
    )
    (net (code "78") (name "unconnected-(U2-XTAL_N_NC-Pad44)") (class "Default")
      (node (ref "U2") (pin "44") (pinfunction "XTAL_N_NC_44") (pintype "passive"))
    )
    (net (code "79") (name "unconnected-(U2-XTAL_P_NC-Pad45)") (class "Default")
      (node (ref "U2") (pin "45") (pinfunction "XTAL_P_NC_45") (pintype "passive"))
    )
    (net (code "80") (name "unconnected-(U4-NC-Pad21)") (class "Default")
      (node (ref "U4") (pin "21") (pinfunction "NC_21") (pintype "passive"))
    )
    (net (code "81") (name "unconnected-(U5-A_CL-Pad7)") (class "Default")
      (node (ref "U5") (pin "7") (pinfunction "A_CL_7") (pintype "passive"))
    )
    (net (code "82") (name "unconnected-(U5-A_DA-Pad6)") (class "Default")
      (node (ref "U5") (pin "6") (pinfunction "A_DA_6") (pintype "passive"))
    )
    (net (code "83") (name "unconnected-(U5-CLKOUT-Pad22)") (class "Default")
      (node (ref "U5") (pin "22") (pinfunction "CLKOUT_22") (pintype "passive"))
    )
    (net (code "84") (name "unconnected-(U5-INT-Pad12)") (class "Default")
      (node (ref "U5") (pin "12") (pinfunction "INT_12") (pintype "passive"))
    )
    (net (code "85") (name "unconnected-(U5-NC-Pad2)") (class "Default")
      (node (ref "U5") (pin "2") (pinfunction "NC_2") (pintype "passive"))
    )
    (net (code "86") (name "unconnected-(U5-NC-Pad3)") (class "Default")
      (node (ref "U5") (pin "3") (pinfunction "NC_3") (pintype "passive"))
    )
    (net (code "87") (name "unconnected-(U5-NC-Pad4)") (class "Default")
      (node (ref "U5") (pin "4") (pinfunction "NC_4") (pintype "passive"))
    )
    (net (code "88") (name "unconnected-(U5-NC-Pad5)") (class "Default")
      (node (ref "U5") (pin "5") (pinfunction "NC_5") (pintype "passive"))
    )
    (net (code "89") (name "unconnected-(U5-NC-Pad14)") (class "Default")
      (node (ref "U5") (pin "14") (pinfunction "NC_14") (pintype "passive"))
    )
    (net (code "90") (name "unconnected-(U5-NC-Pad15)") (class "Default")
      (node (ref "U5") (pin "15") (pinfunction "NC_15") (pintype "passive"))
    )
    (net (code "91") (name "unconnected-(U5-NC-Pad16)") (class "Default")
      (node (ref "U5") (pin "16") (pinfunction "NC_16") (pintype "passive"))
    )
    (net (code "92") (name "unconnected-(U5-NC-Pad17)") (class "Default")
      (node (ref "U5") (pin "17") (pinfunction "NC_17") (pintype "passive"))
    )
    (net (code "93") (name "unconnected-(U5-RESV-Pad19)") (class "Default")
      (node (ref "U5") (pin "19") (pinfunction "RESV_19") (pintype "passive"))
    )
    (net (code "94") (name "unconnected-(U5-RESV-Pad21)") (class "Default")
      (node (ref "U5") (pin "21") (pinfunction "RESV_21") (pintype "passive"))
    )
  )
)
